# Sheet1.net
KiCad netlist of a schematic drawn in Altium Designer
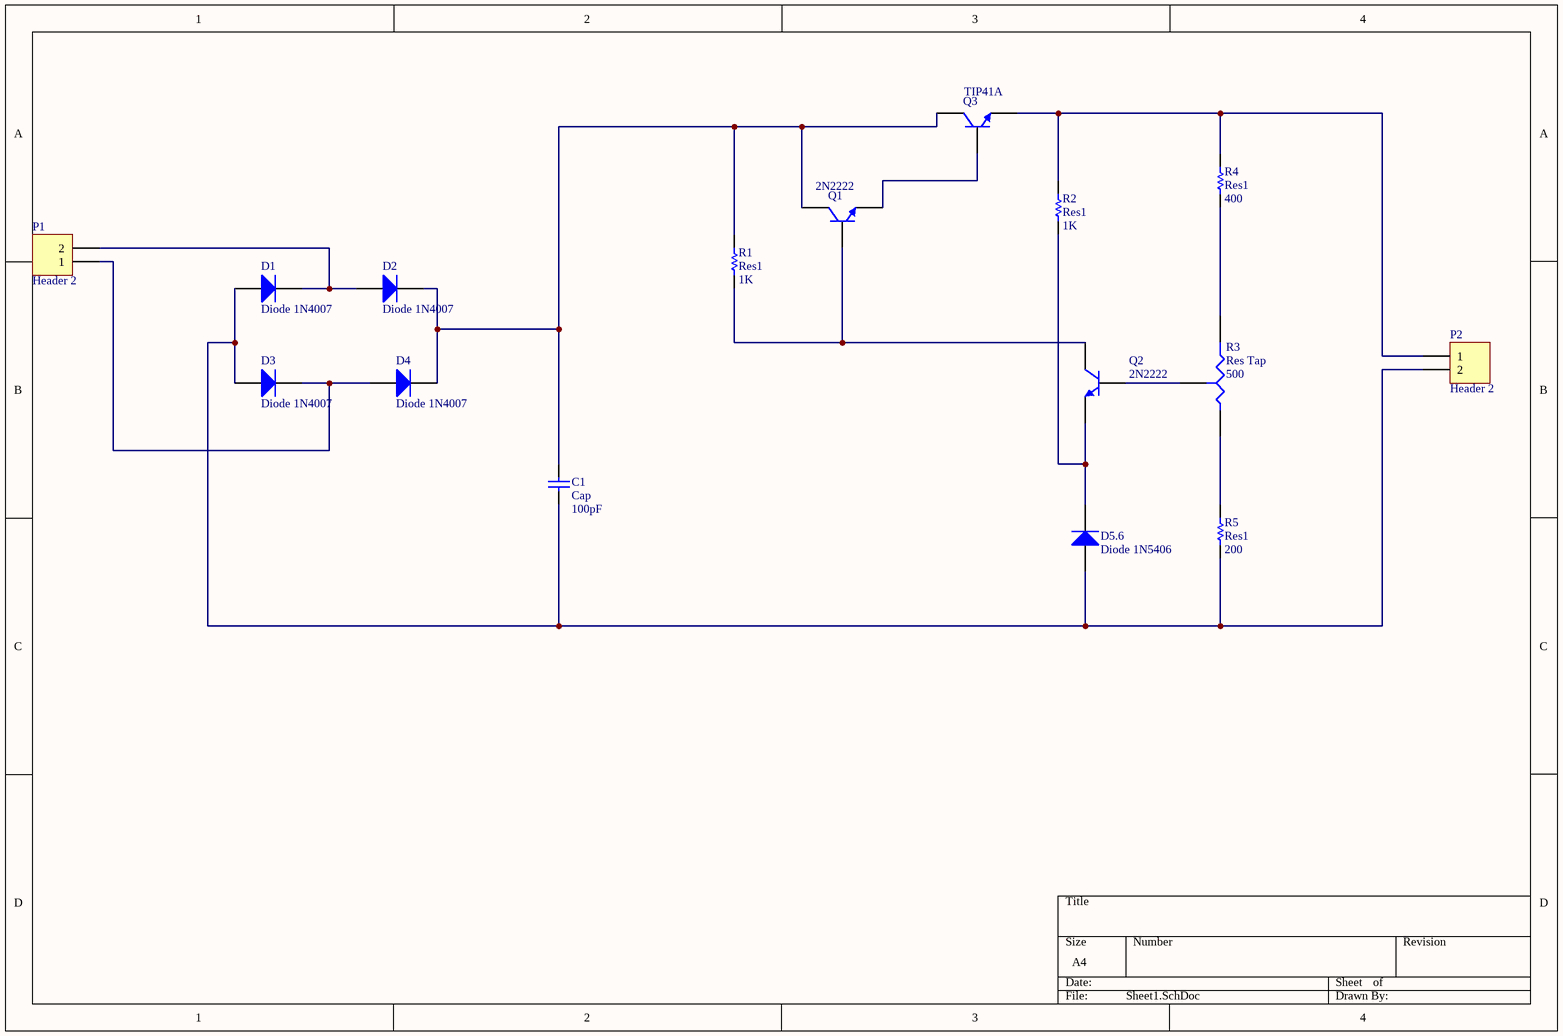
[diagram p0: Sheet1.SchDoc]

(export (version "E")
  (design (tool "Eeschema 10.0.6"))
  (components
    (comp (ref "C1")
      (value "Cap")
      (footprint "RAD-0.3")
      (description "Capacitor")
      (fields (field (name "ALTIUM_VALUE") "100pF") (field (name "PUBLISHER") "Altium Limited"))
      (libsource (lib "Miscellaneous Devices") (part "Cap"))
    )
    (comp (ref "D1")
      (value "Diode 1N4007")
      (footprint "AXIAL-0.3")
      (description "1 Amp General Purpose Rectifier")
      (fields (field (name "PUBLISHER") "Altium Limited"))
      (libsource (lib "Miscellaneous Devices") (part "Diode 1N4007"))
    )
    (comp (ref "D2")
      (value "Diode 1N4007")
      (footprint "AXIAL-0.3")
      (description "1 Amp General Purpose Rectifier")
      (fields (field (name "PUBLISHER") "Altium Limited"))
      (libsource (lib "Miscellaneous Devices") (part "Diode 1N4007"))
    )
    (comp (ref "D3")
      (value "Diode 1N4007")
      (footprint "AXIAL-0.3")
      (description "1 Amp General Purpose Rectifier")
      (fields (field (name "PUBLISHER") "Altium Limited"))
      (libsource (lib "Miscellaneous Devices") (part "Diode 1N4007"))
    )
    (comp (ref "D4")
      (value "Diode 1N4007")
      (footprint "AXIAL-0.3")
      (description "1 Amp General Purpose Rectifier")
      (fields (field (name "PUBLISHER") "Altium Limited"))
      (libsource (lib "Miscellaneous Devices") (part "Diode 1N4007"))
    )
    (comp (ref "D5.6")
      (value "Diode 1N5406")
      (footprint "AXIAL-0.3")
      (description "3 Amp General Purpose Rectifier")
      (fields (field (name "PUBLISHER") "Altium Limited"))
      (libsource (lib "Miscellaneous Devices") (part "Diode 1N5406"))
    )
    (comp (ref "P1")
      (value "Header 2")
      (footprint "HDR1X2")
      (description "Header, 2-Pin")
      (fields (field (name "PUBLISHER") "Altium Limited"))
      (libsource (lib "Miscellaneous Connectors") (part "Header 2"))
    )
    (comp (ref "P2")
      (value "Header 2")
      (footprint "HDR1X2")
      (description "Header, 2-Pin")
      (fields (field (name "PUBLISHER") "Altium Limited"))
      (libsource (lib "") (part "Header 2_1"))
    )
    (comp (ref "Q1")
      (value "2N2222")
      (footprint "TO-39")
      (description "NPN Bipolar Transistor")
      (fields (field (name "PUBLISHER") "Altium Limited"))
      (libsource (lib "Miscellaneous Devices") (part "NPN"))
    )
    (comp (ref "Q2")
      (value "2N2222")
      (footprint "TO-39")
      (description "NPN Bipolar Transistor")
      (fields (field (name "PUBLISHER") "Altium Limited"))
      (libsource (lib "Miscellaneous Devices") (part "NPN"))
    )
    (comp (ref "Q3")
      (value "TIP41A")
      (footprint "TO-220AB")
      (description "NPN Bipolar Transistor")
      (fields (field (name "PUBLISHER") "Altium Limited"))
      (libsource (lib "") (part "NPN_1"))
    )
    (comp (ref "R1")
      (value "Res1")
      (footprint "AXIAL-0.3")
      (description "Resistor")
      (fields (field (name "ALTIUM_VALUE") "1K") (field (name "PUBLISHER") "Altium Limited"))
      (libsource (lib "Miscellaneous Devices") (part "Res1"))
    )
    (comp (ref "R2")
      (value "Res1")
      (footprint "AXIAL-0.3")
      (description "Resistor")
      (fields (field (name "ALTIUM_VALUE") "1K") (field (name "PUBLISHER") "Altium Limited"))
      (libsource (lib "Miscellaneous Devices") (part "Res1"))
    )
    (comp (ref "R3")
      (value "Res Tap")
      (footprint "TO-39")
      (description "Tapped Resistor")
      (fields (field (name "ALTIUM_VALUE") "500") (field (name "PUBLISHER") "Altium Limited"))
      (libsource (lib "Miscellaneous Devices") (part "Res Tap"))
    )
    (comp (ref "R4")
      (value "Res1")
      (footprint "AXIAL-0.3")
      (description "Resistor")
      (fields (field (name "ALTIUM_VALUE") "400") (field (name "PUBLISHER") "Altium Limited"))
      (libsource (lib "Miscellaneous Devices") (part "Res1"))
    )
    (comp (ref "R5")
      (value "Res1")
      (footprint "AXIAL-0.3")
      (description "Resistor")
      (fields (field (name "ALTIUM_VALUE") "200") (field (name "PUBLISHER") "Altium Limited"))
      (libsource (lib "Miscellaneous Devices") (part "Res1"))
    )
  )
  (nets
    (net (code "1") (name "Net-(D1-A)") (class "Default")
      (node (ref "C1") (pin "1") (pinfunction "1_1") (pintype "passive"))
      (node (ref "D1") (pin "1") (pinfunction "A_1") (pintype "passive"))
      (node (ref "D3") (pin "1") (pinfunction "A_1") (pintype "passive"))
      (node (ref "D5.6") (pin "1") (pinfunction "A_1") (pintype "passive"))
      (node (ref "P2") (pin "2") (pinfunction "2_2") (pintype "passive"))
      (node (ref "R5") (pin "1") (pinfunction "1_1") (pintype "passive"))
    )
    (net (code "2") (name "Net-(D1-K)") (class "Default")
      (node (ref "D1") (pin "2") (pinfunction "K_2") (pintype "passive"))
      (node (ref "D2") (pin "1") (pinfunction "A_1") (pintype "passive"))
      (node (ref "P1") (pin "2") (pinfunction "2_2") (pintype "passive"))
    )
    (net (code "3") (name "Net-(D2-K)") (class "Default")
      (node (ref "C1") (pin "2") (pinfunction "2_2") (pintype "passive"))
      (node (ref "D2") (pin "2") (pinfunction "K_2") (pintype "passive"))
      (node (ref "D4") (pin "2") (pinfunction "K_2") (pintype "passive"))
      (node (ref "Q1") (pin "1") (pinfunction "C_1") (pintype "passive"))
      (node (ref "Q3") (pin "1") (pinfunction "B_1") (pintype "passive"))
      (node (ref "R1") (pin "2") (pinfunction "2_2") (pintype "passive"))
    )
    (net (code "4") (name "Net-(D3-K)") (class "Default")
      (node (ref "D3") (pin "2") (pinfunction "K_2") (pintype "passive"))
      (node (ref "D4") (pin "1") (pinfunction "A_1") (pintype "passive"))
      (node (ref "P1") (pin "1") (pinfunction "1_1") (pintype "passive"))
    )
    (net (code "5") (name "Net-(D5.6-K)") (class "Default")
      (node (ref "D5.6") (pin "2") (pinfunction "K_2") (pintype "passive"))
      (node (ref "Q2") (pin "3") (pinfunction "E_3") (pintype "passive"))
      (node (ref "R2") (pin "1") (pinfunction "1_1") (pintype "passive"))
    )
    (net (code "6") (name "Net-(Q1-B)") (class "Default")
      (node (ref "Q1") (pin "2") (pinfunction "B_2") (pintype "passive"))
      (node (ref "Q2") (pin "1") (pinfunction "C_1") (pintype "passive"))
      (node (ref "R1") (pin "1") (pinfunction "1_1") (pintype "passive"))
    )
    (net (code "7") (name "Net-(Q1-E)") (class "Default")
      (node (ref "Q1") (pin "3") (pinfunction "E_3") (pintype "passive"))
      (node (ref "Q3") (pin "2") (pinfunction "C_2") (pintype "passive"))
    )
    (net (code "8") (name "Net-(Q2-B)") (class "Default")
      (node (ref "Q2") (pin "2") (pinfunction "B_2") (pintype "passive"))
      (node (ref "R3") (pin "3") (pinfunction "TAP_3") (pintype "passive"))
    )
    (net (code "9") (name "Net-(Q3-E)") (class "Default")
      (node (ref "P2") (pin "1") (pinfunction "1_1") (pintype "passive"))
      (node (ref "Q3") (pin "3") (pinfunction "E_3") (pintype "passive"))
      (node (ref "R2") (pin "2") (pinfunction "2_2") (pintype "passive"))
      (node (ref "R4") (pin "2") (pinfunction "2_2") (pintype "passive"))
    )
    (net (code "10") (name "Net-(R3-A)") (class "Default")
      (node (ref "R3") (pin "1") (pinfunction "A_1") (pintype "passive"))
      (node (ref "R5") (pin "2") (pinfunction "2_2") (pintype "passive"))
    )
    (net (code "11") (name "Net-(R3-B)") (class "Default")
      (node (ref "R3") (pin "2") (pinfunction "B_2") (pintype "passive"))
      (node (ref "R4") (pin "1") (pinfunction "1_1") (pintype "passive"))
    )
  )
)
